# LED20-A1-P01.net
KiCad netlist of a schematic drawn in Altium Designer
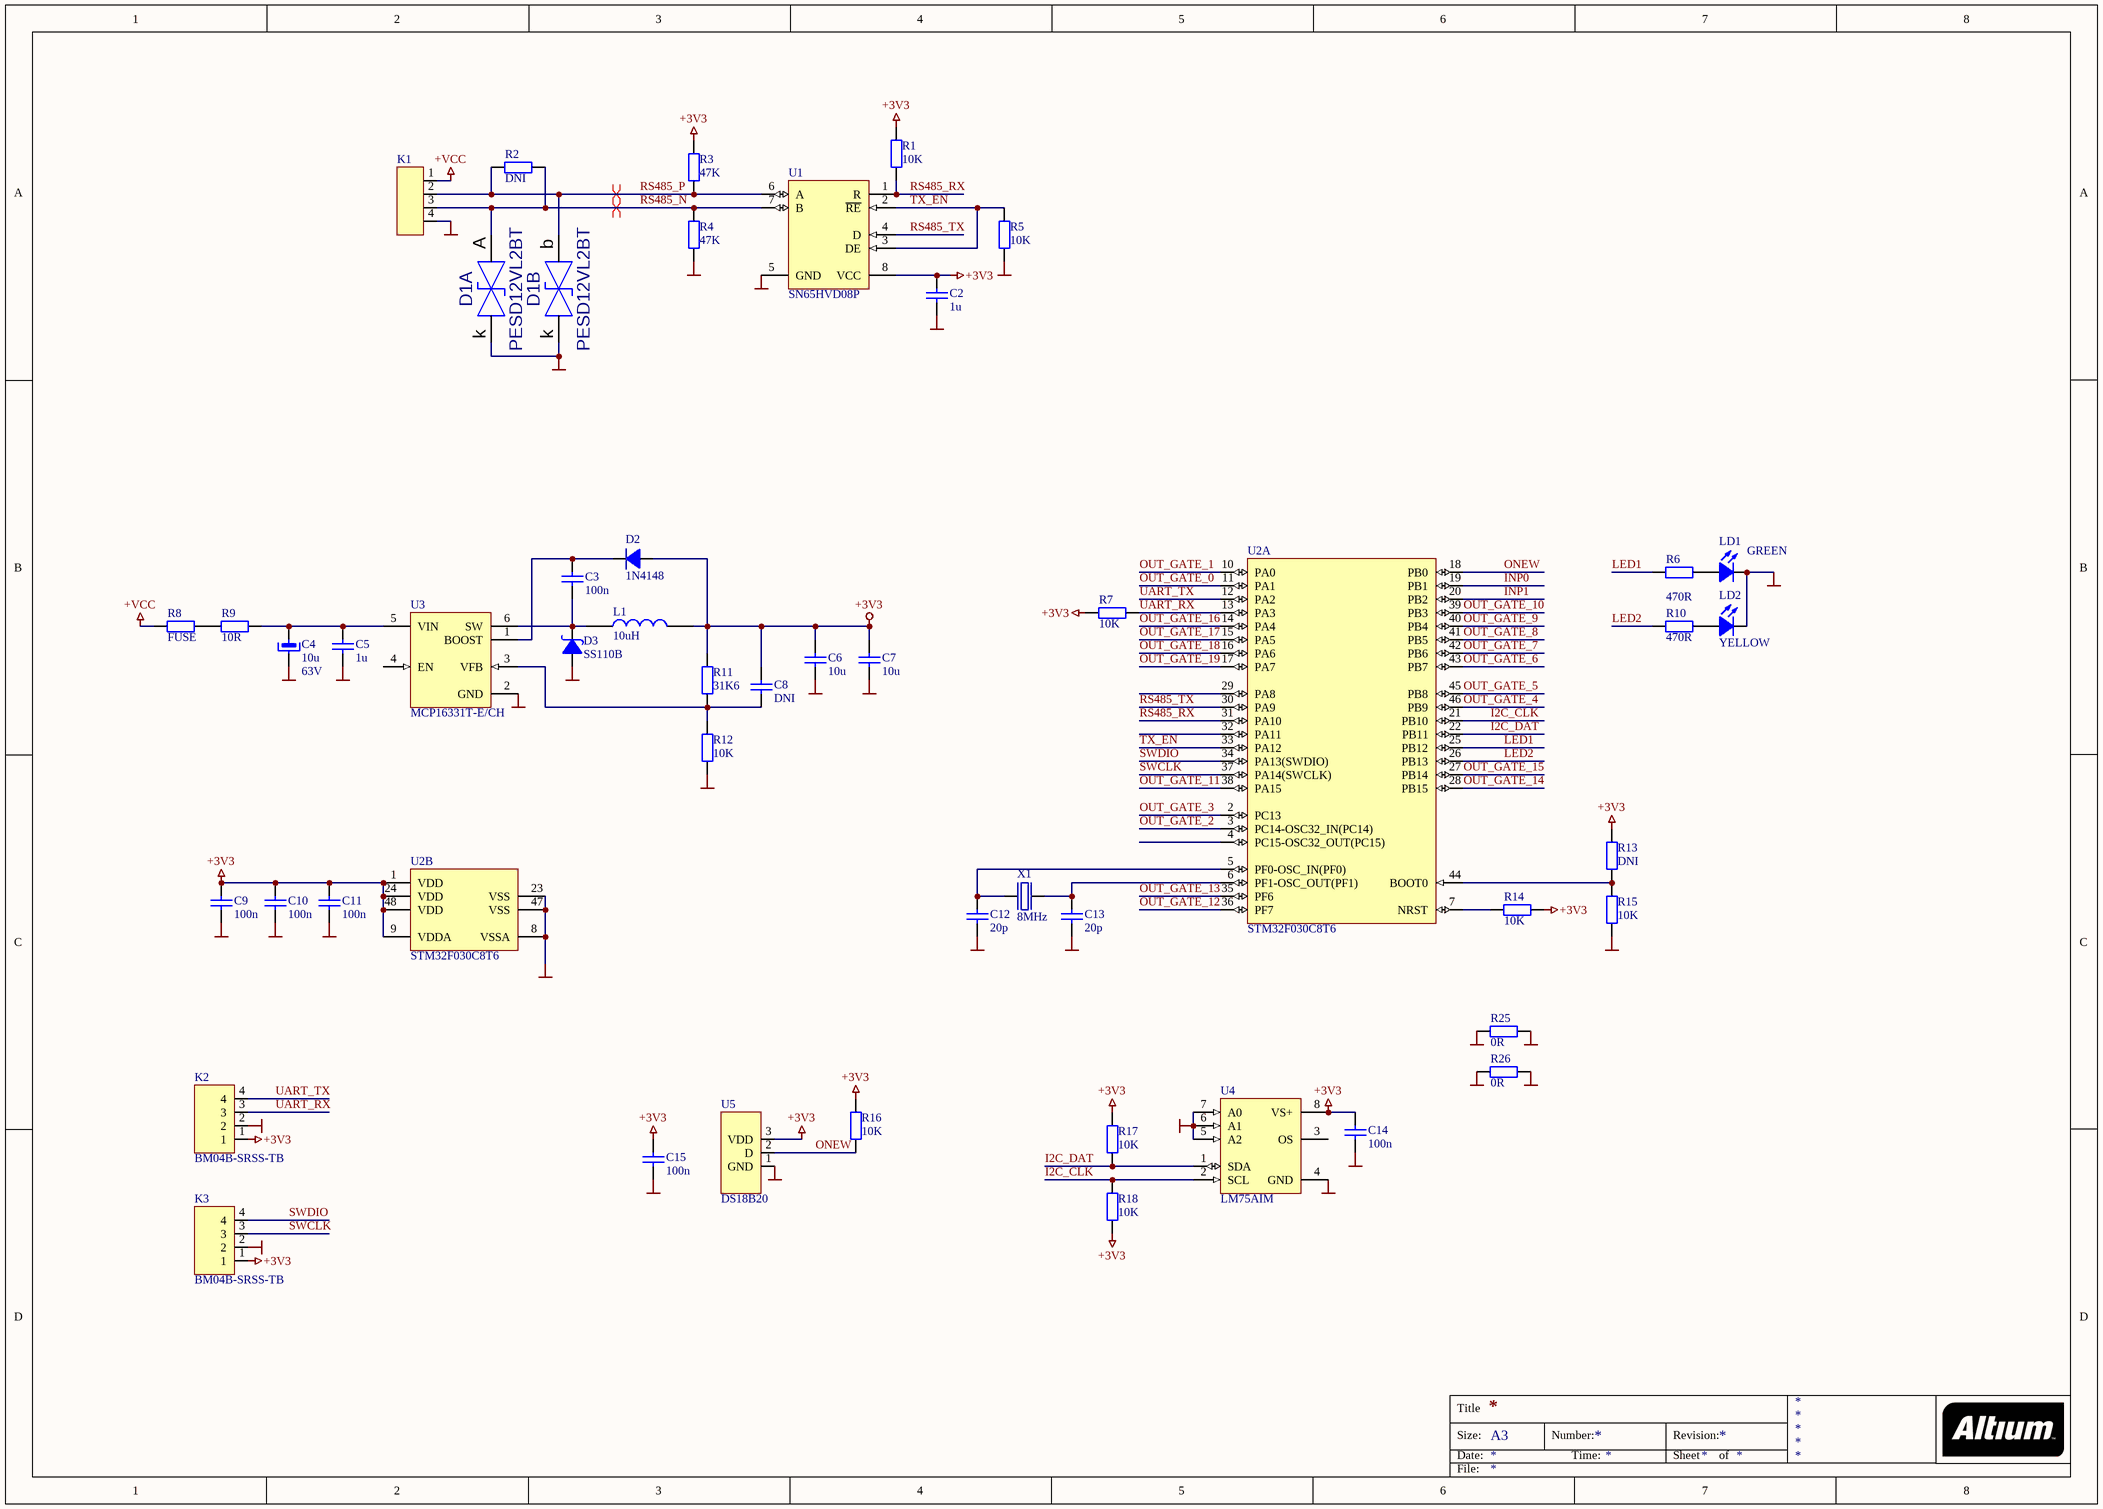
[diagram p0: LED20-A1-P01.SchDoc]

(export (version "E")
  (design (tool "Eeschema 10.0.6"))
  (components
    (comp (ref "C2")
      (value "1u")
      (footprint "Passive:CC0805-1")
      (description "Capacitor chip ceramic 0805")
      (libsource (lib "CapChipCer") (part "CAPCC0805_1U50VX7R"))
    )
    (comp (ref "C3")
      (value "100n")
      (footprint "Passive:CC0805-1")
      (description "Capacitor chip ceramic 0805")
      (libsource (lib "CapChipCer") (part "CAPCC0805_1U50VX7R"))
    )
    (comp (ref "C4")
      (value "10u")
      (footprint "CAPPS-D6.3X7.7")
      (description "Capacitor electrolitic SMD 6.3X6.3X7.7MM low ESR")
      (fields (field (name "COMMENT2") "63V"))
      (libsource (lib "CapElectTht") (part "CAPPS100U25VFP"))
    )
    (comp (ref "C5")
      (value "1u")
      (footprint "Passive:CC0805-1")
      (description "Capacitor chip ceramic 0805")
      (libsource (lib "CapChipCer") (part "CAPCC0805_1U50VX7R"))
    )
    (comp (ref "C6")
      (value "10u")
      (footprint "CC0805-1")
      (description "Capacitor chip ceramic 0805")
      (libsource (lib "CapChipCer") (part "CAPCC0805_10U16VX5R"))
    )
    (comp (ref "C7")
      (value "10u")
      (footprint "CC0805-1")
      (description "Capacitor chip ceramic 0805")
      (libsource (lib "CapChipCer") (part "CAPCC0805_10U16VX5R"))
    )
    (comp (ref "C8")
      (value "DNI")
      (footprint "Passive:CC0805-1")
      (description "Capacitor chip ceramic 0805")
      (libsource (lib "CapChipCer") (part "CAPCC0805_1U50VX7R"))
    )
    (comp (ref "C9")
      (value "100n")
      (footprint "CC0805-1")
      (description "Capacitor chip ceramic 0805")
      (libsource (lib "CapChipCer") (part "CAPCC0805_100N50VX7R"))
    )
    (comp (ref "C10")
      (value "100n")
      (footprint "CC0805-1")
      (description "Capacitor chip ceramic 0805")
      (libsource (lib "CapChipCer") (part "CAPCC0805_100N50VX7R"))
    )
    (comp (ref "C11")
      (value "100n")
      (footprint "CC0805-1")
      (description "Capacitor chip ceramic 0805")
      (libsource (lib "CapChipCer") (part "CAPCC0805_100N50VX7R"))
    )
    (comp (ref "C12")
      (value "20p")
      (footprint "CC0805-1")
      (description "Capacitor chip ceramic 0805")
      (libsource (lib "CapChipCer") (part "CAPCC0805_100N50VX7R"))
    )
    (comp (ref "C13")
      (value "20p")
      (footprint "CC0805-1")
      (description "Capacitor chip ceramic 0805")
      (libsource (lib "CapChipCer") (part "CAPCC0805_100N50VX7R"))
    )
    (comp (ref "C14")
      (value "100n")
      (footprint "CC0805-1")
      (description "Capacitor chip ceramic 0805")
      (libsource (lib "CapChipCer") (part "CAPCC0805_100N50VX7R"))
    )
    (comp (ref "C15")
      (value "100n")
      (footprint "CC0805-1")
      (description "Capacitor chip ceramic 0805")
      (libsource (lib "CapChipCer") (part "CAPCC0805_100N50VX7R"))
    )
    (comp (ref "D1")
      (value "PESD12VL2BT")
      (footprint "SOT-23_NUP2105L(Primary)")
      (description "Diode")
      (libsource (lib "fractal_lib") (part "NUP2105L"))
    )
    (comp (ref "D2")
      (value "1N4148")
      (footprint "Passive:SOD-123")
      (description "Small Signal Diode")
      (fields (field (name "MANUFACTURER") "Vishay"))
      (libsource (lib "Discrete") (part "D-1N4148WS"))
    )
    (comp (ref "D3")
      (value "SS110B")
      (footprint "Passive:DO-214AC")
      (description "Schottky Diode")
      (fields (field (name "MANUFACTURER") "multicomp"))
      (libsource (lib "Discrete") (part "CD214A-B240LF-0.3V@1A"))
    )
    (comp (ref "K1")
      (value "Terminal Block Connector, 3.81mm, Right Angle")
      (footprint "CONN_3.81_4")
      (description "Terminal Block Connector, 3.81mm, 4pin")
      (libsource (lib "fractal_lib") (part "CONN_TB_3.81_4PIN"))
    )
    (comp (ref "K2")
      (value "BM04B-SRSS-TB")
      (footprint "JST-SH-4pin")
      (description "JST connector 4pin vertical")
      (libsource (lib "fractal_lib") (part "JST-SH-BM04B-SRSS-TB"))
    )
    (comp (ref "K3")
      (value "BM04B-SRSS-TB")
      (footprint "JST-SH-4pin")
      (description "JST connector 4pin vertical")
      (libsource (lib "fractal_lib") (part "JST-SH-BM04B-SRSS-TB"))
    )
    (comp (ref "L1")
      (value "10uH")
      (footprint "IND-LQH32CN4R7M33l")
      (description "Chip Inductor 4 x 4 mm")
      (fields (field (name "MANUFACTURER") "Murata"))
      (libsource (lib "Induct") (part "LQH44PN100MP0L"))
    )
    (comp (ref "LD1")
      (value "GREEN")
      (footprint "Active:LEDGREENC190")
      (description "LED green HSMG vertical")
      (fields (field (name "MANUFACTURER") "Avago"))
      (libsource (lib "Discrete") (part "LED-GREEN0603V"))
    )
    (comp (ref "LD2")
      (value "YELLOW")
      (footprint "Active:LEDYELLOWC190")
      (description "LED yellow HSMY vertical")
      (fields (field (name "MANUFACTURER") "Avago"))
      (libsource (lib "Discrete") (part "LED-YELLOW0603V"))
    )
    (comp (ref "R1")
      (value "10K")
      (footprint "RC0805-1")
      (description "Chip Resistor 0805")
      (libsource (lib "") (part "RES0805_2"))
    )
    (comp (ref "R2")
      (value "DNI")
      (footprint "RC0805-1")
      (description "Chip Resistor 0805")
      (libsource (lib "") (part "RES0805_2"))
    )
    (comp (ref "R3")
      (value "47K")
      (footprint "RC0805-1")
      (description "Chip Resistor 0805")
      (libsource (lib "") (part "RES0805_1"))
    )
    (comp (ref "R4")
      (value "47K")
      (footprint "RC0805-1")
      (description "Chip Resistor 0805")
      (libsource (lib "") (part "RES0805_1"))
    )
    (comp (ref "R5")
      (value "10K")
      (footprint "RC0805-1")
      (description "Chip Resistor 0805")
      (libsource (lib "") (part "RES0805_2"))
    )
    (comp (ref "R6")
      (value "470R")
      (footprint "RC0805-1")
      (description "Chip Resistor 0805")
      (libsource (lib "") (part "RES0805_2"))
    )
    (comp (ref "R7")
      (value "10K")
      (footprint "RC0805-1")
      (description "Chip Resistor 0805")
      (libsource (lib "") (part "RES0805_2"))
    )
    (comp (ref "R8")
      (value "FUSE")
      (footprint "RC1206-1")
      (description "Chip Resistor 1206")
      (libsource (lib "Resistors") (part "RES1206"))
    )
    (comp (ref "R9")
      (value "10R")
      (footprint "RC0805-1")
      (description "Chip Resistor 0805")
      (libsource (lib "") (part "RES0805_3"))
    )
    (comp (ref "R10")
      (value "470R")
      (footprint "RC0805-1")
      (description "Chip Resistor 0805")
      (libsource (lib "") (part "RES0805_2"))
    )
    (comp (ref "R11")
      (value "31K6")
      (footprint "RC0805-1")
      (description "Chip Resistor 0805")
      (libsource (lib "") (part "RES0805_1"))
    )
    (comp (ref "R12")
      (value "10K")
      (footprint "RC0805-1")
      (description "Chip Resistor 0805")
      (libsource (lib "") (part "RES0805_1"))
    )
    (comp (ref "R13")
      (value "DNI")
      (footprint "RC0805-1")
      (description "Chip Resistor 0805")
      (libsource (lib "") (part "RES0805_1"))
    )
    (comp (ref "R14")
      (value "10K")
      (footprint "RC0805-1")
      (description "Chip Resistor 0805")
      (libsource (lib "") (part "RES0805_3"))
    )
    (comp (ref "R15")
      (value "10K")
      (footprint "RC0805-1")
      (description "Chip Resistor 0805")
      (libsource (lib "Resistors") (part "RES0805"))
    )
    (comp (ref "R16")
      (value "10K")
      (footprint "RC0805-1")
      (description "Chip Resistor 0805")
      (libsource (lib "Resistors") (part "RES0805"))
    )
    (comp (ref "R17")
      (value "10K")
      (footprint "RC0805-1")
      (description "Chip Resistor 0805")
      (libsource (lib "Resistors") (part "RES0805"))
    )
    (comp (ref "R18")
      (value "10K")
      (footprint "RC0805-1")
      (description "Chip Resistor 0805")
      (libsource (lib "") (part "RES0805_1"))
    )
    (comp (ref "R25")
      (value "0R")
      (footprint "RC0805-1")
      (description "Chip Resistor 0805")
      (libsource (lib "") (part "RES0805_2"))
    )
    (comp (ref "R26")
      (value "0R")
      (footprint "RC0805-1")
      (description "Chip Resistor 0805")
      (libsource (lib "") (part "RES0805_2"))
    )
    (comp (ref "U1")
      (value "SN65HVD08P")
      (footprint "M08A_M")
      (description "3.3 / 5 V RS-485 Transceiver, 10 Mbps, Half Duplex, -40 to 85 degC, 8-pin PDIP (P), Pb-Free (RoHS)")
      (fields (field (name "MANUFACTURER") "Texas Instruments"))
      (libsource (lib "fractal_lib") (part "SN65HVD08P"))
    )
    (comp (ref "U2")
      (value "STM32F030C8T6")
      (footprint "STM-LQFP48_N")
      (libsource (lib "fractal_lib") (part "STM32F030C8T6"))
    )
    (comp (ref "U3")
      (value "MCP16331T-E/CH")
      (footprint "MCHP-SOT-23-CH6_N")
      (fields (field (name "MANUFACTURER") "Microchip"))
      (libsource (lib "fractal_lib") (part "MCP16301T-E/CH"))
    )
    (comp (ref "U4")
      (value "LM75AIM")
      (footprint "M08A_N")
      (description "Digital Temperature Sensor and Thermal Watchdog with Two-Wire Interface, 8-pin Narrow SOIC")
      (fields (field (name "MANUFACTURER") "National Semiconductor"))
      (libsource (lib "fractal_lib") (part "LM75AIM"))
    )
    (comp (ref "U5")
      (value "DS18B20")
      (footprint "TO92")
      (description "digital temperature sensor")
      (libsource (lib "fractal_lib") (part "DS18B20"))
    )
    (comp (ref "X1")
      (value "8MHz")
      (footprint "OSCCC150X320X9-2N")
      (description "SMD Crystal 8MHz")
      (libsource (lib "fractal_lib") (part "XTAL-SMD_8MHz"))
    )
  )
  (nets
    (net (code "1") (name "+3V3") (class "Default")
      (node (ref "C10") (pin "2") (pinfunction "2_2") (pintype "passive"))
      (node (ref "C11") (pin "2") (pinfunction "2_2") (pintype "passive"))
      (node (ref "C14") (pin "2") (pinfunction "2_2") (pintype "passive"))
      (node (ref "C15") (pin "2") (pinfunction "2_2") (pintype "passive"))
      (node (ref "C2") (pin "2") (pinfunction "2_2") (pintype "passive"))
      (node (ref "C6") (pin "2") (pinfunction "2_2") (pintype "passive"))
      (node (ref "C7") (pin "2") (pinfunction "2_2") (pintype "passive"))
      (node (ref "C8") (pin "2") (pinfunction "2_2") (pintype "passive"))
      (node (ref "C9") (pin "2") (pinfunction "2_2") (pintype "passive"))
      (node (ref "D2") (pin "2") (pinfunction "A_2") (pintype "passive"))
      (node (ref "K2") (pin "1") (pinfunction "1_1") (pintype "passive"))
      (node (ref "K3") (pin "1") (pinfunction "1_1") (pintype "passive"))
      (node (ref "L1") (pin "2") (pinfunction "2_2") (pintype "passive"))
      (node (ref "R1") (pin "2") (pinfunction "2_2") (pintype "passive"))
      (node (ref "R11") (pin "2") (pinfunction "2_2") (pintype "passive"))
      (node (ref "R13") (pin "2") (pinfunction "2_2") (pintype "passive"))
      (node (ref "R14") (pin "1") (pinfunction "1_1") (pintype "passive"))
      (node (ref "R16") (pin "1") (pinfunction "1_1") (pintype "passive"))
      (node (ref "R17") (pin "1") (pinfunction "1_1") (pintype "passive"))
      (node (ref "R18") (pin "1") (pinfunction "1_1") (pintype "passive"))
      (node (ref "R3") (pin "2") (pinfunction "2_2") (pintype "passive"))
      (node (ref "R7") (pin "1") (pinfunction "1_1") (pintype "passive"))
      (node (ref "U1") (pin "8") (pinfunction "VCC_8") (pintype "power_in"))
      (node (ref "U2") (pin "1") (pinfunction "VDD_1") (pintype "power_in"))
      (node (ref "U2") (pin "24") (pinfunction "VDD_24") (pintype "power_in"))
      (node (ref "U2") (pin "48") (pinfunction "VDD_48") (pintype "power_in"))
      (node (ref "U2") (pin "9") (pinfunction "VDDA_9") (pintype "power_in"))
      (node (ref "U4") (pin "8") (pinfunction "VS+_8") (pintype "power_in"))
      (node (ref "U5") (pin "3") (pinfunction "VDD_3") (pintype "passive"))
    )
    (net (code "2") (name "+VCC") (class "Default")
      (node (ref "K1") (pin "1") (pinfunction "A_1") (pintype "passive"))
      (node (ref "R8") (pin "1") (pinfunction "1_1") (pintype "passive"))
    )
    (net (code "3") (name "/I2C_CLK") (class "Default")
      (node (ref "R18") (pin "2") (pinfunction "2_2") (pintype "passive"))
      (node (ref "U2") (pin "21") (pinfunction "PB10_21") (pintype "bidirectional"))
      (node (ref "U4") (pin "2") (pinfunction "SCL_2") (pintype "input"))
    )
    (net (code "4") (name "/I2C_DAT") (class "Default")
      (node (ref "R17") (pin "2") (pinfunction "2_2") (pintype "passive"))
      (node (ref "U2") (pin "22") (pinfunction "PB11_22") (pintype "bidirectional"))
      (node (ref "U4") (pin "1") (pinfunction "SDA_1") (pintype "bidirectional"))
    )
    (net (code "5") (name "/INP0") (class "Default")
      (node (ref "U2") (pin "19") (pinfunction "PB1_19") (pintype "bidirectional"))
    )
    (net (code "6") (name "/INP1") (class "Default")
      (node (ref "U2") (pin "20") (pinfunction "PB2_20") (pintype "bidirectional"))
    )
    (net (code "7") (name "/LED1") (class "Default")
      (node (ref "R6") (pin "1") (pinfunction "1_1") (pintype "passive"))
      (node (ref "U2") (pin "25") (pinfunction "PB12_25") (pintype "bidirectional"))
    )
    (net (code "8") (name "/LED2") (class "Default")
      (node (ref "R10") (pin "1") (pinfunction "1_1") (pintype "passive"))
      (node (ref "U2") (pin "26") (pinfunction "PB13_26") (pintype "bidirectional"))
    )
    (net (code "9") (name "/ONEW") (class "Default")
      (node (ref "R16") (pin "2") (pinfunction "2_2") (pintype "passive"))
      (node (ref "U2") (pin "18") (pinfunction "PB0_18") (pintype "bidirectional"))
      (node (ref "U5") (pin "2") (pinfunction "D_2") (pintype "passive"))
    )
    (net (code "10") (name "/OUT_GATE_0") (class "Default")
      (node (ref "U2") (pin "11") (pinfunction "PA1_11") (pintype "bidirectional"))
    )
    (net (code "11") (name "/OUT_GATE_1") (class "Default")
      (node (ref "U2") (pin "10") (pinfunction "PA0_10") (pintype "bidirectional"))
    )
    (net (code "12") (name "/OUT_GATE_2") (class "Default")
      (node (ref "U2") (pin "3") (pinfunction "PC14-OSC32_IN(PC14)_3") (pintype "bidirectional"))
    )
    (net (code "13") (name "/OUT_GATE_3") (class "Default")
      (node (ref "U2") (pin "2") (pinfunction "PC13_2") (pintype "bidirectional"))
    )
    (net (code "14") (name "/OUT_GATE_4") (class "Default")
      (node (ref "U2") (pin "46") (pinfunction "PB9_46") (pintype "bidirectional"))
    )
    (net (code "15") (name "/OUT_GATE_5") (class "Default")
      (node (ref "U2") (pin "45") (pinfunction "PB8_45") (pintype "bidirectional"))
    )
    (net (code "16") (name "/OUT_GATE_6") (class "Default")
      (node (ref "U2") (pin "43") (pinfunction "PB7_43") (pintype "bidirectional"))
    )
    (net (code "17") (name "/OUT_GATE_7") (class "Default")
      (node (ref "U2") (pin "42") (pinfunction "PB6_42") (pintype "bidirectional"))
    )
    (net (code "18") (name "/OUT_GATE_8") (class "Default")
      (node (ref "U2") (pin "41") (pinfunction "PB5_41") (pintype "bidirectional"))
    )
    (net (code "19") (name "/OUT_GATE_9") (class "Default")
      (node (ref "U2") (pin "40") (pinfunction "PB4_40") (pintype "bidirectional"))
    )
    (net (code "20") (name "/OUT_GATE_10") (class "Default")
      (node (ref "U2") (pin "39") (pinfunction "PB3_39") (pintype "bidirectional"))
    )
    (net (code "21") (name "/OUT_GATE_11") (class "Default")
      (node (ref "U2") (pin "38") (pinfunction "PA15_38") (pintype "bidirectional"))
    )
    (net (code "22") (name "/OUT_GATE_12") (class "Default")
      (node (ref "U2") (pin "36") (pinfunction "PF7_36") (pintype "bidirectional"))
    )
    (net (code "23") (name "/OUT_GATE_13") (class "Default")
      (node (ref "U2") (pin "35") (pinfunction "PF6_35") (pintype "bidirectional"))
    )
    (net (code "24") (name "/OUT_GATE_14") (class "Default")
      (node (ref "U2") (pin "28") (pinfunction "PB15_28") (pintype "bidirectional"))
    )
    (net (code "25") (name "/OUT_GATE_15") (class "Default")
      (node (ref "U2") (pin "27") (pinfunction "PB14_27") (pintype "bidirectional"))
    )
    (net (code "26") (name "/OUT_GATE_16") (class "Default")
      (node (ref "U2") (pin "14") (pinfunction "PA4_14") (pintype "bidirectional"))
    )
    (net (code "27") (name "/OUT_GATE_17") (class "Default")
      (node (ref "U2") (pin "15") (pinfunction "PA5_15") (pintype "bidirectional"))
    )
    (net (code "28") (name "/OUT_GATE_18") (class "Default")
      (node (ref "U2") (pin "16") (pinfunction "PA6_16") (pintype "bidirectional"))
    )
    (net (code "29") (name "/OUT_GATE_19") (class "Default")
      (node (ref "U2") (pin "17") (pinfunction "PA7_17") (pintype "bidirectional"))
    )
    (net (code "30") (name "/RS485_N") (class "Default")
      (node (ref "D1") (pin "A") (pinfunction "A_A") (pintype "passive"))
      (node (ref "K1") (pin "3") (pinfunction "A_3") (pintype "passive"))
      (node (ref "R2") (pin "2") (pinfunction "2_2") (pintype "passive"))
      (node (ref "R4") (pin "2") (pinfunction "2_2") (pintype "passive"))
      (node (ref "U1") (pin "7") (pinfunction "B_7") (pintype "bidirectional"))
    )
    (net (code "31") (name "/RS485_P") (class "Default")
      (node (ref "D1") (pin "b") (pinfunction "A_b") (pintype "passive"))
      (node (ref "K1") (pin "2") (pinfunction "K_2") (pintype "passive"))
      (node (ref "R2") (pin "1") (pinfunction "1_1") (pintype "passive"))
      (node (ref "R3") (pin "1") (pinfunction "1_1") (pintype "passive"))
      (node (ref "U1") (pin "6") (pinfunction "A_6") (pintype "bidirectional"))
    )
    (net (code "32") (name "/RS485_RX") (class "Default")
      (node (ref "R1") (pin "1") (pinfunction "1_1") (pintype "passive"))
      (node (ref "U1") (pin "1") (pinfunction "R_1") (pintype "tri_state"))
      (node (ref "U2") (pin "31") (pinfunction "PA10_31") (pintype "bidirectional"))
    )
    (net (code "33") (name "/RS485_TX") (class "Default")
      (node (ref "U1") (pin "4") (pinfunction "D_4") (pintype "input"))
      (node (ref "U2") (pin "30") (pinfunction "PA9_30") (pintype "bidirectional"))
    )
    (net (code "34") (name "/SWCLK") (class "Default")
      (node (ref "K3") (pin "3") (pinfunction "3_3") (pintype "passive"))
      (node (ref "U2") (pin "37") (pinfunction "PA14(SWCLK)_37") (pintype "bidirectional"))
    )
    (net (code "35") (name "/SWDIO") (class "Default")
      (node (ref "K3") (pin "4") (pinfunction "4_4") (pintype "passive"))
      (node (ref "U2") (pin "34") (pinfunction "PA13(SWDIO)_34") (pintype "bidirectional"))
    )
    (net (code "36") (name "/TX_EN") (class "Default")
      (node (ref "R5") (pin "2") (pinfunction "2_2") (pintype "passive"))
      (node (ref "U1") (pin "2") (pinfunction "~{RE}_2") (pintype "input"))
      (node (ref "U1") (pin "3") (pinfunction "DE_3") (pintype "input"))
      (node (ref "U2") (pin "33") (pinfunction "PA12_33") (pintype "bidirectional"))
    )
    (net (code "37") (name "/UART_RX") (class "Default")
      (node (ref "K2") (pin "3") (pinfunction "3_3") (pintype "passive"))
      (node (ref "R7") (pin "2") (pinfunction "2_2") (pintype "passive"))
      (node (ref "U2") (pin "13") (pinfunction "PA3_13") (pintype "bidirectional"))
    )
    (net (code "38") (name "/UART_TX") (class "Default")
      (node (ref "K2") (pin "4") (pinfunction "4_4") (pintype "passive"))
      (node (ref "U2") (pin "12") (pinfunction "PA2_12") (pintype "bidirectional"))
    )
    (net (code "39") (name "GND") (class "Default")
      (node (ref "C10") (pin "1") (pinfunction "1_1") (pintype "passive"))
      (node (ref "C11") (pin "1") (pinfunction "1_1") (pintype "passive"))
      (node (ref "C12") (pin "1") (pinfunction "1_1") (pintype "passive"))
      (node (ref "C13") (pin "1") (pinfunction "1_1") (pintype "passive"))
      (node (ref "C14") (pin "1") (pinfunction "1_1") (pintype "passive"))
      (node (ref "C15") (pin "1") (pinfunction "1_1") (pintype "passive"))
      (node (ref "C2") (pin "1") (pinfunction "1_1") (pintype "passive"))
      (node (ref "C4") (pin "2") (pinfunction "2_2") (pintype "passive"))
      (node (ref "C5") (pin "1") (pinfunction "1_1") (pintype "passive"))
      (node (ref "C6") (pin "1") (pinfunction "1_1") (pintype "passive"))
      (node (ref "C7") (pin "1") (pinfunction "1_1") (pintype "passive"))
      (node (ref "C9") (pin "1") (pinfunction "1_1") (pintype "passive"))
      (node (ref "D1") (pin "k") (pinfunction "K_k") (pintype "power_in"))
      (node (ref "D3") (pin "A") (pinfunction "A_A") (pintype "passive"))
      (node (ref "K1") (pin "4") (pinfunction "K_4") (pintype "passive"))
      (node (ref "K2") (pin "2") (pinfunction "2_2") (pintype "passive"))
      (node (ref "K3") (pin "2") (pinfunction "2_2") (pintype "passive"))
      (node (ref "LD1") (pin "1") (pinfunction "C_1") (pintype "passive"))
      (node (ref "LD2") (pin "1") (pinfunction "C_1") (pintype "passive"))
      (node (ref "R12") (pin "1") (pinfunction "1_1") (pintype "passive"))
      (node (ref "R15") (pin "2") (pinfunction "2_2") (pintype "passive"))
      (node (ref "R25") (pin "1") (pinfunction "1_1") (pintype "passive"))
      (node (ref "R25") (pin "2") (pinfunction "2_2") (pintype "passive"))
      (node (ref "R26") (pin "1") (pinfunction "1_1") (pintype "passive"))
      (node (ref "R26") (pin "2") (pinfunction "2_2") (pintype "passive"))
      (node (ref "R4") (pin "1") (pinfunction "1_1") (pintype "passive"))
      (node (ref "R5") (pin "1") (pinfunction "1_1") (pintype "passive"))
      (node (ref "U1") (pin "5") (pinfunction "GND_5") (pintype "power_in"))
      (node (ref "U2") (pin "23") (pinfunction "VSS_23") (pintype "power_in"))
      (node (ref "U2") (pin "47") (pinfunction "VSS_47") (pintype "power_in"))
      (node (ref "U2") (pin "8") (pinfunction "VSSA_8") (pintype "power_in"))
      (node (ref "U3") (pin "2") (pinfunction "GND_2") (pintype "power_in"))
      (node (ref "U4") (pin "4") (pinfunction "GND_4") (pintype "power_in"))
      (node (ref "U4") (pin "5") (pinfunction "A2_5") (pintype "input"))
      (node (ref "U4") (pin "6") (pinfunction "A1_6") (pintype "input"))
      (node (ref "U4") (pin "7") (pinfunction "A0_7") (pintype "input"))
      (node (ref "U5") (pin "1") (pinfunction "GND_1") (pintype "passive"))
    )
    (net (code "40") (name "Net-(D2-C)") (class "Default")
      (node (ref "C3") (pin "2") (pinfunction "2_2") (pintype "passive"))
      (node (ref "D2") (pin "1") (pinfunction "C_1") (pintype "passive"))
      (node (ref "U3") (pin "1") (pinfunction "BOOST_1") (pintype "power_in"))
    )
    (net (code "41") (name "Net-(LD1-A)") (class "Default")
      (node (ref "LD1") (pin "2") (pinfunction "A_2") (pintype "passive"))
      (node (ref "R6") (pin "2") (pinfunction "2_2") (pintype "passive"))
    )
    (net (code "42") (name "Net-(LD2-A)") (class "Default")
      (node (ref "LD2") (pin "2") (pinfunction "A_2") (pintype "passive"))
      (node (ref "R10") (pin "2") (pinfunction "2_2") (pintype "passive"))
    )
    (net (code "43") (name "Net-(R8-Pad2)") (class "Default")
      (node (ref "R8") (pin "2") (pinfunction "2_2") (pintype "passive"))
      (node (ref "R9") (pin "2") (pinfunction "2_2") (pintype "passive"))
    )
    (net (code "44") (name "Net-(U2A-BOOT0)") (class "Default")
      (node (ref "R13") (pin "1") (pinfunction "1_1") (pintype "passive"))
      (node (ref "R15") (pin "1") (pinfunction "1_1") (pintype "passive"))
      (node (ref "U2") (pin "44") (pinfunction "BOOT0_44") (pintype "input"))
    )
    (net (code "45") (name "Net-(U2A-NRST)") (class "Default")
      (node (ref "R14") (pin "2") (pinfunction "2_2") (pintype "passive"))
      (node (ref "U2") (pin "7") (pinfunction "NRST_7") (pintype "bidirectional"))
    )
    (net (code "46") (name "Net-(U2A-PF0-OSC_IN(PF0))") (class "Default")
      (node (ref "C12") (pin "2") (pinfunction "2_2") (pintype "passive"))
      (node (ref "U2") (pin "5") (pinfunction "PF0-OSC_IN(PF0)_5") (pintype "bidirectional"))
      (node (ref "X1") (pin "1") (pinfunction "OUT_1") (pintype "power_in"))
    )
    (net (code "47") (name "Net-(U2A-PF1-OSC_OUT(PF1))") (class "Default")
      (node (ref "C13") (pin "2") (pinfunction "2_2") (pintype "passive"))
      (node (ref "U2") (pin "6") (pinfunction "PF1-OSC_OUT(PF1)_6") (pintype "bidirectional"))
      (node (ref "X1") (pin "2") (pinfunction "IN_2") (pintype "passive"))
    )
    (net (code "48") (name "Net-(U3-SW)") (class "Default")
      (node (ref "C3") (pin "1") (pinfunction "1_1") (pintype "passive"))
      (node (ref "D3") (pin "K") (pinfunction "K_K") (pintype "passive"))
      (node (ref "L1") (pin "1") (pinfunction "1_1") (pintype "passive"))
      (node (ref "U3") (pin "6") (pinfunction "SW_6") (pintype "power_in"))
    )
    (net (code "49") (name "Net-(U3-VFB)") (class "Default")
      (node (ref "C8") (pin "1") (pinfunction "1_1") (pintype "passive"))
      (node (ref "R11") (pin "1") (pinfunction "1_1") (pintype "passive"))
      (node (ref "R12") (pin "2") (pinfunction "2_2") (pintype "passive"))
      (node (ref "U3") (pin "3") (pinfunction "VFB_3") (pintype "input"))
    )
    (net (code "50") (name "Net-(U3-VIN)") (class "Default")
      (node (ref "C4") (pin "1") (pinfunction "1_1") (pintype "passive"))
      (node (ref "C5") (pin "2") (pinfunction "2_2") (pintype "passive"))
      (node (ref "R9") (pin "1") (pinfunction "1_1") (pintype "passive"))
      (node (ref "U3") (pin "5") (pinfunction "VIN_5") (pintype "power_in"))
    )
    (net (code "51") (name "unconnected-(U2A-PA8-Pad29)") (class "Default")
      (node (ref "U2") (pin "29") (pinfunction "PA8_29") (pintype "bidirectional"))
    )
    (net (code "52") (name "unconnected-(U2A-PA11-Pad32)") (class "Default")
      (node (ref "U2") (pin "32") (pinfunction "PA11_32") (pintype "bidirectional"))
    )
    (net (code "53") (name "unconnected-(U2A-PC15-OSC32_OUT(PC15)-Pad4)") (class "Default")
      (node (ref "U2") (pin "4") (pinfunction "PC15-OSC32_OUT(PC15)_4") (pintype "bidirectional"))
    )
    (net (code "54") (name "unconnected-(U3-EN-Pad4)") (class "Default")
      (node (ref "U3") (pin "4") (pinfunction "EN_4") (pintype "input"))
    )
    (net (code "55") (name "unconnected-(U4-OS-Pad3)") (class "Default")
      (node (ref "U4") (pin "3") (pinfunction "OS_3") (pintype "open_collector"))
    )
  )
)
